# Main.net
KiCad netlist of a schematic drawn in Altium Designer
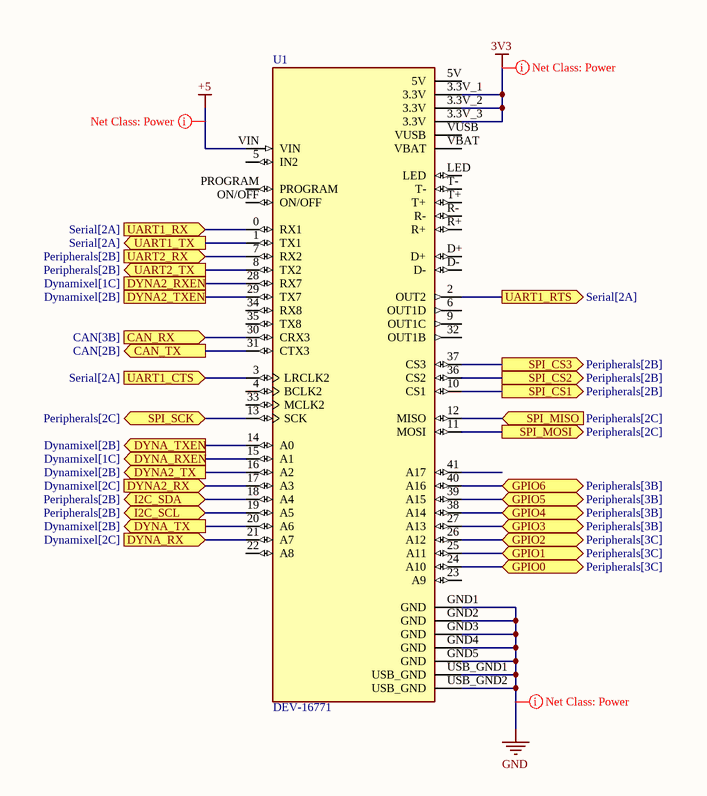
[diagram p0: Main.SchDoc]

(export (version "E")
  (design (tool "Eeschema 10.0.6"))
  (components
    (comp (ref "U1")
      (value "DEV-16771")
      (footprint "DEV-16771:MODULE_DEV-16771")
      (description "RT1062 Teensy 4.1 i.MX ARM Cortex-M7 MPU Embedded Evaluation Board")
      (fields (field (name "MF") "{'manufacturer': u'SparkFun Electronics'}"))
      (libsource (lib "*") (part "DEV-16771"))
    )
  )
  (nets
    (net (code "1") (name "+5") (class "Default")
      (node (ref "U1") (pin "VIN") (pinfunction "VIN_VIN") (pintype "input"))
    )
    (net (code "2") (name "/CAN_RX") (class "Default")
      (node (ref "U1") (pin "30") (pinfunction "CRX3_30") (pintype "bidirectional"))
    )
    (net (code "3") (name "/CAN_TX") (class "Default")
      (node (ref "U1") (pin "31") (pinfunction "CTX3_31") (pintype "bidirectional"))
    )
    (net (code "4") (name "/DYNA2_RX") (class "Default")
      (node (ref "U1") (pin "17") (pinfunction "A3_17") (pintype "bidirectional"))
    )
    (net (code "5") (name "/DYNA2_RXEN") (class "Default")
      (node (ref "U1") (pin "28") (pinfunction "RX7_28") (pintype "bidirectional"))
    )
    (net (code "6") (name "/DYNA2_TX") (class "Default")
      (node (ref "U1") (pin "16") (pinfunction "A2_16") (pintype "bidirectional"))
    )
    (net (code "7") (name "/DYNA2_TXEN") (class "Default")
      (node (ref "U1") (pin "29") (pinfunction "TX7_29") (pintype "bidirectional"))
    )
    (net (code "8") (name "/DYNA_RX") (class "Default")
      (node (ref "U1") (pin "21") (pinfunction "A7_21") (pintype "bidirectional"))
    )
    (net (code "9") (name "/DYNA_RXEN") (class "Default")
      (node (ref "U1") (pin "15") (pinfunction "A1_15") (pintype "bidirectional"))
    )
    (net (code "10") (name "/DYNA_TX") (class "Default")
      (node (ref "U1") (pin "20") (pinfunction "A6_20") (pintype "bidirectional"))
    )
    (net (code "11") (name "/DYNA_TXEN") (class "Default")
      (node (ref "U1") (pin "14") (pinfunction "A0_14") (pintype "bidirectional"))
    )
    (net (code "12") (name "/GPIO0") (class "Default")
      (node (ref "U1") (pin "24") (pinfunction "A10_24") (pintype "bidirectional"))
    )
    (net (code "13") (name "/GPIO1") (class "Default")
      (node (ref "U1") (pin "25") (pinfunction "A11_25") (pintype "bidirectional"))
    )
    (net (code "14") (name "/GPIO2") (class "Default")
      (node (ref "U1") (pin "26") (pinfunction "A12_26") (pintype "bidirectional"))
    )
    (net (code "15") (name "/GPIO3") (class "Default")
      (node (ref "U1") (pin "27") (pinfunction "A13_27") (pintype "bidirectional"))
    )
    (net (code "16") (name "/GPIO4") (class "Default")
      (node (ref "U1") (pin "38") (pinfunction "A14_38") (pintype "bidirectional"))
    )
    (net (code "17") (name "/GPIO5") (class "Default")
      (node (ref "U1") (pin "39") (pinfunction "A15_39") (pintype "bidirectional"))
    )
    (net (code "18") (name "/GPIO6") (class "Default")
      (node (ref "U1") (pin "40") (pinfunction "A16_40") (pintype "bidirectional"))
    )
    (net (code "19") (name "/I2C_SCL") (class "Default")
      (node (ref "U1") (pin "19") (pinfunction "A5_19") (pintype "bidirectional"))
    )
    (net (code "20") (name "/I2C_SDA") (class "Default")
      (node (ref "U1") (pin "18") (pinfunction "A4_18") (pintype "bidirectional"))
    )
    (net (code "21") (name "/SPI_CS1") (class "Default")
      (node (ref "U1") (pin "10") (pinfunction "CS1_10") (pintype "bidirectional"))
    )
    (net (code "22") (name "/SPI_CS2") (class "Default")
      (node (ref "U1") (pin "36") (pinfunction "CS2_36") (pintype "bidirectional"))
    )
    (net (code "23") (name "/SPI_CS3") (class "Default")
      (node (ref "U1") (pin "37") (pinfunction "CS3_37") (pintype "bidirectional"))
    )
    (net (code "24") (name "/SPI_MISO") (class "Default")
      (node (ref "U1") (pin "12") (pinfunction "MISO_12") (pintype "bidirectional"))
    )
    (net (code "25") (name "/SPI_MOSI") (class "Default")
      (node (ref "U1") (pin "11") (pinfunction "MOSI_11") (pintype "bidirectional"))
    )
    (net (code "26") (name "/SPI_SCK") (class "Default")
      (node (ref "U1") (pin "13") (pinfunction "SCK_13") (pintype "bidirectional"))
    )
    (net (code "27") (name "/UART1_CTS") (class "Default")
      (node (ref "U1") (pin "3") (pinfunction "LRCLK2_3") (pintype "bidirectional"))
    )
    (net (code "28") (name "/UART1_RTS") (class "Default")
      (node (ref "U1") (pin "2") (pinfunction "OUT2_2") (pintype "output"))
    )
    (net (code "29") (name "/UART1_RX") (class "Default")
      (node (ref "U1") (pin "0") (pinfunction "RX1_0") (pintype "bidirectional"))
    )
    (net (code "30") (name "/UART1_TX") (class "Default")
      (node (ref "U1") (pin "1") (pinfunction "TX1_1") (pintype "bidirectional"))
    )
    (net (code "31") (name "/UART2_RX") (class "Default")
      (node (ref "U1") (pin "7") (pinfunction "RX2_7") (pintype "bidirectional"))
    )
    (net (code "32") (name "/UART2_TX") (class "Default")
      (node (ref "U1") (pin "8") (pinfunction "TX2_8") (pintype "bidirectional"))
    )
    (net (code "33") (name "3V3") (class "Default")
      (node (ref "U1") (pin "3.3V_1") (pinfunction "3.3V_3.3V_1") (pintype "power_in"))
      (node (ref "U1") (pin "3.3V_2") (pinfunction "3.3V_3.3V_2") (pintype "power_in"))
      (node (ref "U1") (pin "3.3V_3") (pinfunction "3.3V_3.3V_3") (pintype "power_in"))
    )
    (net (code "34") (name "GND") (class "Default")
      (node (ref "U1") (pin "GND1") (pinfunction "GND_GND1") (pintype "power_in"))
      (node (ref "U1") (pin "GND2") (pinfunction "GND_GND2") (pintype "power_in"))
      (node (ref "U1") (pin "GND3") (pinfunction "GND_GND3") (pintype "power_in"))
      (node (ref "U1") (pin "GND4") (pinfunction "GND_GND4") (pintype "power_in"))
      (node (ref "U1") (pin "GND5") (pinfunction "GND_GND5") (pintype "power_in"))
      (node (ref "U1") (pin "USB_GND1") (pinfunction "USB_GND_USB_GND1") (pintype "power_in"))
      (node (ref "U1") (pin "USB_GND2") (pinfunction "USB_GND_USB_GND2") (pintype "power_in"))
    )
    (net (code "35") (name "unconnected-(U1-A8-Pad22)") (class "Default")
      (node (ref "U1") (pin "22") (pinfunction "A8_22") (pintype "bidirectional"))
    )
    (net (code "36") (name "unconnected-(U1-A9-Pad23)") (class "Default")
      (node (ref "U1") (pin "23") (pinfunction "A9_23") (pintype "bidirectional"))
    )
    (net (code "37") (name "unconnected-(U1-A17-Pad41)") (class "Default")
      (node (ref "U1") (pin "41") (pinfunction "A17_41") (pintype "bidirectional"))
    )
    (net (code "38") (name "unconnected-(U1-BCLK2-Pad4)") (class "Default")
      (node (ref "U1") (pin "4") (pinfunction "BCLK2_4") (pintype "bidirectional"))
    )
    (net (code "39") (name "unconnected-(U1-IN2-Pad5)") (class "Default")
      (node (ref "U1") (pin "5") (pinfunction "IN2_5") (pintype "bidirectional"))
    )
    (net (code "40") (name "unconnected-(U1-MCLK2-Pad33)") (class "Default")
      (node (ref "U1") (pin "33") (pinfunction "MCLK2_33") (pintype "bidirectional"))
    )
    (net (code "41") (name "unconnected-(U1-OUT1B-Pad32)") (class "Default")
      (node (ref "U1") (pin "32") (pinfunction "OUT1B_32") (pintype "output"))
    )
    (net (code "42") (name "unconnected-(U1-OUT1C-Pad9)") (class "Default")
      (node (ref "U1") (pin "9") (pinfunction "OUT1C_9") (pintype "output"))
    )
    (net (code "43") (name "unconnected-(U1-OUT1D-Pad6)") (class "Default")
      (node (ref "U1") (pin "6") (pinfunction "OUT1D_6") (pintype "output"))
    )
    (net (code "44") (name "unconnected-(U1-Pad5V)") (class "Default")
      (node (ref "U1") (pin "5V") (pinfunction "5V_5V") (pintype "power_in"))
    )
    (net (code "45") (name "unconnected-(U1-PadD+)") (class "Default")
      (node (ref "U1") (pin "D+") (pinfunction "D+_D+") (pintype "bidirectional"))
    )
    (net (code "46") (name "unconnected-(U1-PadD-)") (class "Default")
      (node (ref "U1") (pin "D-") (pinfunction "D-_D-") (pintype "bidirectional"))
    )
    (net (code "47") (name "unconnected-(U1-PadLED)") (class "Default")
      (node (ref "U1") (pin "LED") (pinfunction "LED_LED") (pintype "bidirectional"))
    )
    (net (code "48") (name "unconnected-(U1-PadON{slash}OFF)") (class "Default")
      (node (ref "U1") (pin "ON/OFF") (pinfunction "ON/OFF_ON/OFF") (pintype "bidirectional"))
    )
    (net (code "49") (name "unconnected-(U1-PadPROGRAM)") (class "Default")
      (node (ref "U1") (pin "PROGRAM") (pinfunction "PROGRAM_PROGRAM") (pintype "bidirectional"))
    )
    (net (code "50") (name "unconnected-(U1-PadR+)") (class "Default")
      (node (ref "U1") (pin "R+") (pinfunction "R+_R+") (pintype "bidirectional"))
    )
    (net (code "51") (name "unconnected-(U1-PadR-)") (class "Default")
      (node (ref "U1") (pin "R-") (pinfunction "R-_R-") (pintype "bidirectional"))
    )
    (net (code "52") (name "unconnected-(U1-PadT+)") (class "Default")
      (node (ref "U1") (pin "T+") (pinfunction "T+_T+") (pintype "bidirectional"))
    )
    (net (code "53") (name "unconnected-(U1-PadT-)") (class "Default")
      (node (ref "U1") (pin "T-") (pinfunction "T-_T-") (pintype "bidirectional"))
    )
    (net (code "54") (name "unconnected-(U1-PadVBAT)") (class "Default")
      (node (ref "U1") (pin "VBAT") (pinfunction "VBAT_VBAT") (pintype "passive"))
    )
    (net (code "55") (name "unconnected-(U1-PadVUSB)") (class "Default")
      (node (ref "U1") (pin "VUSB") (pinfunction "VUSB_VUSB") (pintype "passive"))
    )
    (net (code "56") (name "unconnected-(U1-RX8-Pad34)") (class "Default")
      (node (ref "U1") (pin "34") (pinfunction "RX8_34") (pintype "bidirectional"))
    )
    (net (code "57") (name "unconnected-(U1-TX8-Pad35)") (class "Default")
      (node (ref "U1") (pin "35") (pinfunction "TX8_35") (pintype "bidirectional"))
    )
  )
)
